# miniSystrm.net
KiCad netlist of a schematic drawn in Altium Designer
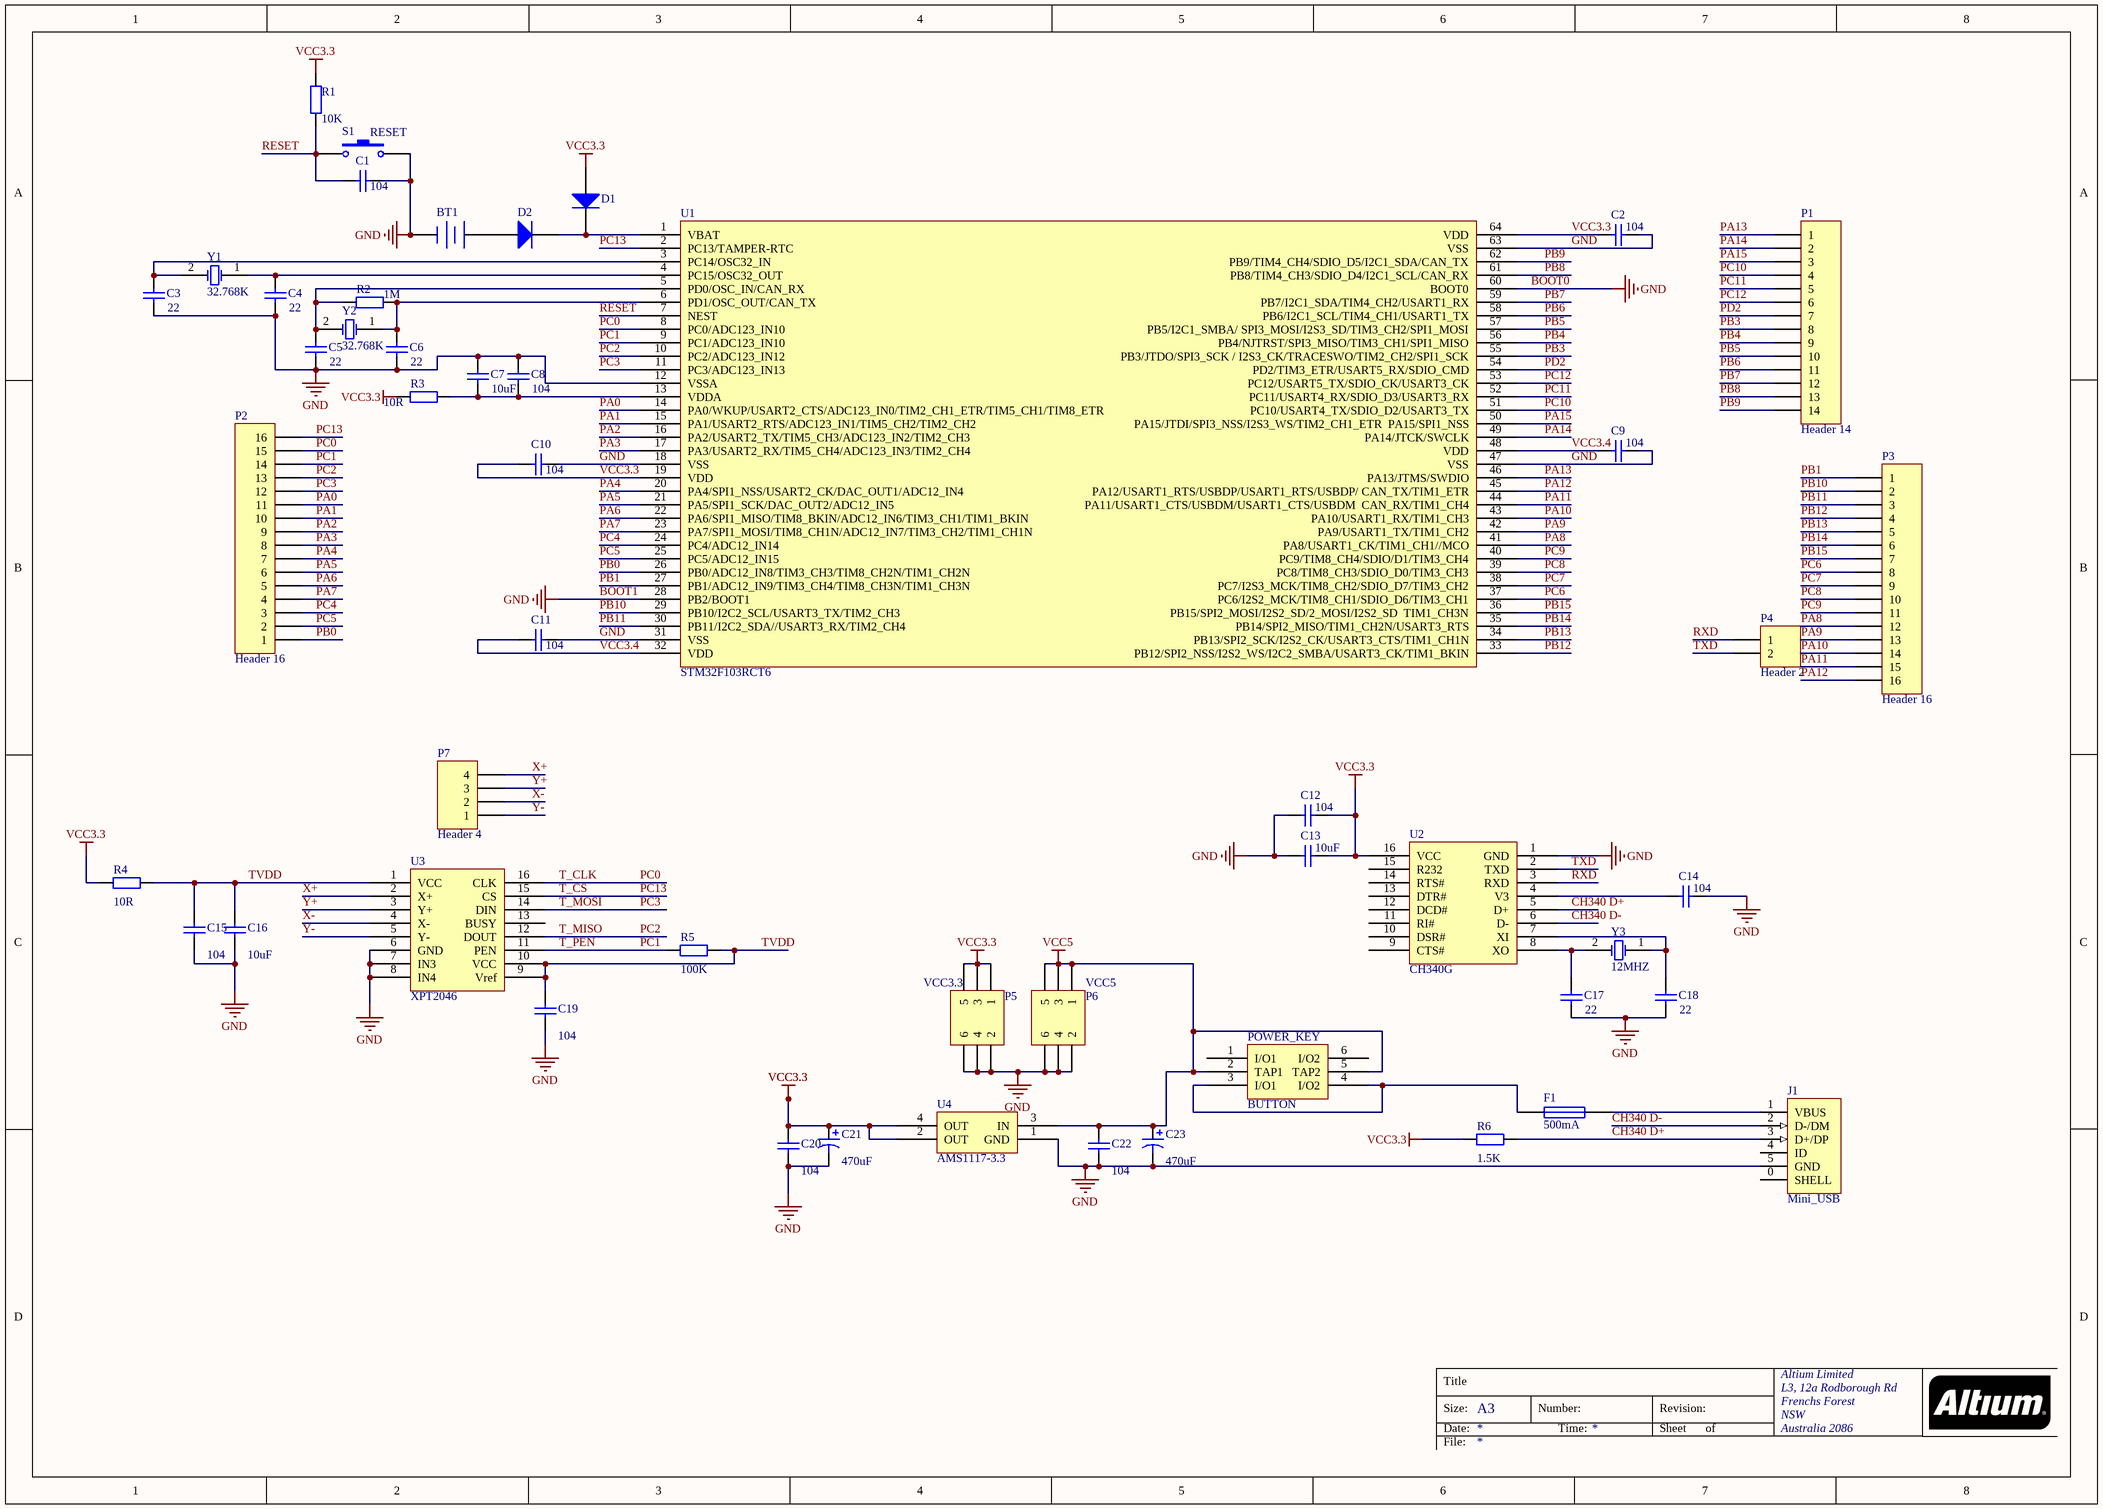
[diagram p0: miniSystrm.SchDoc]

(export (version "E")
  (design (tool "Eeschema 10.0.6"))
  (components
    (comp (ref "BT1")
      (value "~")
      (footprint "BAT-2")
      (description "Multicell Battery")
      (fields (field (name "PUBLISHER") "Altium Limited"))
      (libsource (lib "Miscellaneous Devices") (part "Battery"))
    )
    (comp (ref "C1")
      (value "104")
      (footprint "CAP-0603")
      (description "Capacitor")
      (fields (field (name "PUBLISHER") "Altium Limited"))
      (libsource (lib "Miscellaneous Devices") (part "Cap"))
    )
    (comp (ref "C2")
      (value "104")
      (footprint "CAP-0603")
      (description "Capacitor")
      (fields (field (name "PUBLISHER") "Altium Limited"))
      (libsource (lib "Miscellaneous Devices") (part "Cap"))
    )
    (comp (ref "C3")
      (value "22")
      (footprint "CAP-0603")
      (description "Capacitor")
      (fields (field (name "PUBLISHER") "Altium Limited"))
      (libsource (lib "Miscellaneous Devices") (part "Cap"))
    )
    (comp (ref "C4")
      (value "22")
      (footprint "CAP-0603")
      (description "Capacitor")
      (fields (field (name "PUBLISHER") "Altium Limited"))
      (libsource (lib "Miscellaneous Devices") (part "Cap"))
    )
    (comp (ref "C5")
      (value "22")
      (footprint "CAP-0603")
      (description "Capacitor")
      (fields (field (name "PUBLISHER") "Altium Limited"))
      (libsource (lib "Miscellaneous Devices") (part "Cap"))
    )
    (comp (ref "C6")
      (value "22")
      (footprint "CAP-0603")
      (description "Capacitor")
      (fields (field (name "PUBLISHER") "Altium Limited"))
      (libsource (lib "Miscellaneous Devices") (part "Cap"))
    )
    (comp (ref "C7")
      (value "10uF")
      (footprint "CAP-0603")
      (description "Capacitor")
      (fields (field (name "PUBLISHER") "Altium Limited"))
      (libsource (lib "Miscellaneous Devices") (part "Cap"))
    )
    (comp (ref "C8")
      (value "104")
      (footprint "CAP-0603")
      (description "Capacitor")
      (fields (field (name "PUBLISHER") "Altium Limited"))
      (libsource (lib "Miscellaneous Devices") (part "Cap"))
    )
    (comp (ref "C9")
      (value "104")
      (footprint "CAP-0603")
      (description "Capacitor")
      (fields (field (name "PUBLISHER") "Altium Limited"))
      (libsource (lib "Miscellaneous Devices") (part "Cap"))
    )
    (comp (ref "C10")
      (value "104")
      (footprint "CAP-0603")
      (description "Capacitor")
      (fields (field (name "PUBLISHER") "Altium Limited"))
      (libsource (lib "Miscellaneous Devices") (part "Cap"))
    )
    (comp (ref "C11")
      (value "104")
      (footprint "CAP-0603")
      (description "Capacitor")
      (fields (field (name "PUBLISHER") "Altium Limited"))
      (libsource (lib "Miscellaneous Devices") (part "Cap"))
    )
    (comp (ref "C12")
      (value "104")
      (footprint "CAP-0603")
      (description "Capacitor")
      (fields (field (name "PUBLISHER") "Altium Limited"))
      (libsource (lib "Miscellaneous Devices") (part "Cap"))
    )
    (comp (ref "C13")
      (value "10uF")
      (footprint "CAP-0603")
      (description "Capacitor")
      (fields (field (name "PUBLISHER") "Altium Limited"))
      (libsource (lib "Miscellaneous Devices") (part "Cap"))
    )
    (comp (ref "C14")
      (value "104")
      (footprint "CAP-0603")
      (description "Capacitor")
      (fields (field (name "PUBLISHER") "Altium Limited"))
      (libsource (lib "Miscellaneous Devices") (part "Cap"))
    )
    (comp (ref "C15")
      (value "104")
      (footprint "CAP-0603")
      (description "Capacitor")
      (fields (field (name "PUBLISHER") "Altium Limited"))
      (libsource (lib "Miscellaneous Devices") (part "Cap"))
    )
    (comp (ref "C16")
      (value "10uF")
      (footprint "CAP-0603")
      (description "Capacitor")
      (fields (field (name "PUBLISHER") "Altium Limited"))
      (libsource (lib "Miscellaneous Devices") (part "Cap"))
    )
    (comp (ref "C17")
      (value "22")
      (footprint "CAP-0603")
      (description "Capacitor")
      (fields (field (name "PUBLISHER") "Altium Limited"))
      (libsource (lib "Miscellaneous Devices") (part "Cap"))
    )
    (comp (ref "C18")
      (value "22")
      (footprint "CAP-0603")
      (description "Capacitor")
      (fields (field (name "PUBLISHER") "Altium Limited"))
      (libsource (lib "Miscellaneous Devices") (part "Cap"))
    )
    (comp (ref "C19")
      (value "104")
      (footprint "CAP-0603")
      (description "Capacitor")
      (fields (field (name "PUBLISHER") "Altium Limited"))
      (libsource (lib "Miscellaneous Devices") (part "Cap"))
    )
    (comp (ref "C20")
      (value "104")
      (footprint "CAP-0603")
      (description "Capacitor")
      (fields (field (name "PUBLISHER") "Altium Limited"))
      (libsource (lib "Miscellaneous Devices") (part "Cap"))
    )
    (comp (ref "C21")
      (value "470uF")
      (footprint "CAP-7343")
      (description "Polarized Capacitor (Radial)")
      (fields (field (name "PUBLISHER") "Altium Limited"))
      (libsource (lib "Miscellaneous Devices") (part "Cap Pol1"))
    )
    (comp (ref "C22")
      (value "104")
      (footprint "CAP-0603")
      (description "Capacitor")
      (fields (field (name "PUBLISHER") "Altium Limited"))
      (libsource (lib "Miscellaneous Devices") (part "Cap"))
    )
    (comp (ref "C23")
      (value "470uF")
      (footprint "CAP-7343")
      (description "Polarized Capacitor (Radial)")
      (fields (field (name "PUBLISHER") "Altium Limited"))
      (libsource (lib "Miscellaneous Devices") (part "Cap Pol1"))
    )
    (comp (ref "D1")
      (value "~")
      (footprint "DIODE-SMA")
      (description "1 Amp General Purpose Rectifier")
      (fields (field (name "PUBLISHER") "Altium Limited"))
      (libsource (lib "Miscellaneous Devices") (part "Diode 1N4001"))
    )
    (comp (ref "D2")
      (value "~")
      (footprint "DIODE-SMA")
      (description "1 Amp General Purpose Rectifier")
      (fields (field (name "PUBLISHER") "Altium Limited"))
      (libsource (lib "Miscellaneous Devices") (part "Diode 1N4001"))
    )
    (comp (ref "F1")
      (value "500mA")
      (footprint "PIN-W2/E2.8")
      (description "Fuse")
      (fields (field (name "PUBLISHER") "Altium Limited"))
      (libsource (lib "Miscellaneous Devices") (part "Fuse 1"))
    )
    (comp (ref "J1")
      (value "Mini_USB")
      (footprint "miniUSB")
      (description "USB 2.0, Right Angle, SMT, B Type, Receptacle, 5 Position, Black")
      (fields (field (name "PUBLISHER") "Altium Limited"))
      (libsource (lib "SkyWorks2") (part "Mini_USB"))
    )
    (comp (ref "P1")
      (value "Header 14")
      (footprint "HDR1X14")
      (description "Header, 14-Pin")
      (fields (field (name "PUBLISHER") "Altium Limited"))
      (libsource (lib "Miscellaneous Connectors") (part "Header 14"))
    )
    (comp (ref "P2")
      (value "Header 16")
      (footprint "HDR1X16")
      (description "Header, 16-Pin")
      (fields (field (name "PUBLISHER") "Altium Limited"))
      (libsource (lib "") (part "Header 16_1"))
    )
    (comp (ref "P3")
      (value "Header 16")
      (footprint "HDR1X16")
      (description "Header, 16-Pin")
      (fields (field (name "PUBLISHER") "Altium Limited"))
      (libsource (lib "Miscellaneous Connectors") (part "Header 16"))
    )
    (comp (ref "P4")
      (value "Header 2")
      (footprint "HDR1X2")
      (description "Header, 2-Pin")
      (fields (field (name "PUBLISHER") "Altium Limited"))
      (libsource (lib "Miscellaneous Connectors") (part "Header 2"))
    )
    (comp (ref "P5")
      (value "VCC3.3")
      (footprint "HDR2X3")
      (description "Header, 3-Pin, Dual row")
      (fields (field (name "PUBLISHER") "Altium Limited"))
      (libsource (lib "Miscellaneous Connectors") (part "Header 3X2"))
    )
    (comp (ref "P6")
      (value "VCC5")
      (footprint "HDR2X3")
      (description "Header, 3-Pin, Dual row")
      (fields (field (name "PUBLISHER") "Altium Limited"))
      (libsource (lib "Miscellaneous Connectors") (part "Header 3X2"))
    )
    (comp (ref "P7")
      (value "Header 4")
      (footprint "HDR1X4")
      (description "Header, 4-Pin")
      (fields (field (name "PUBLISHER") "Altium Limited"))
      (libsource (lib "Miscellaneous Connectors") (part "Header 4"))
    )
    (comp (ref "POWER_KEY") (value "BUTTON") (footprint "六脚自锁开关") (libsource (lib "BUTTON") (part "BUTTON")))
    (comp (ref "R1")
      (value "10K")
      (footprint "RES-0603")
      (description "Resistor")
      (fields (field (name "PUBLISHER") "Altium Limited"))
      (libsource (lib "") (part "Res2_2"))
    )
    (comp (ref "R2")
      (value "1M")
      (footprint "RES-0603")
      (description "Resistor")
      (fields (field (name "PUBLISHER") "Altium Limited"))
      (libsource (lib "") (part "Res2_1"))
    )
    (comp (ref "R3")
      (value "10R")
      (footprint "RES-0603")
      (description "Resistor")
      (fields (field (name "PUBLISHER") "Altium Limited"))
      (libsource (lib "Miscellaneous Devices") (part "Res2"))
    )
    (comp (ref "R4")
      (value "10R")
      (footprint "RES-0603")
      (description "Resistor")
      (fields (field (name "PUBLISHER") "Altium Limited"))
      (libsource (lib "Miscellaneous Devices") (part "Res2"))
    )
    (comp (ref "R5")
      (value "100K")
      (footprint "RES-0603")
      (description "Resistor")
      (fields (field (name "PUBLISHER") "Altium Limited"))
      (libsource (lib "Miscellaneous Devices") (part "Res2"))
    )
    (comp (ref "R6")
      (value "1.5K")
      (footprint "RES-0603")
      (description "Resistor")
      (fields (field (name "PUBLISHER") "Altium Limited"))
      (libsource (lib "Miscellaneous Devices") (part "Res2"))
    )
    (comp (ref "S1")
      (value "RESET")
      (footprint "SPST-2")
      (description "Switch")
      (fields (field (name "PUBLISHER") "Altium Limited"))
      (libsource (lib "Miscellaneous Devices") (part "SW-PB"))
    )
    (comp (ref "U1")
      (value "STM32F103RCT6")
      (footprint "LQFP-64")
      (libsource (lib "STM32F103RCT6") (part "STM32F103RCT6"))
    )
    (comp (ref "U2") (value "CH340G") (footprint "SOP16") (libsource (lib "CH340G") (part "CH340G")))
    (comp (ref "U3") (value "XPT2046") (footprint "TSSOP-16") (libsource (lib "XPT2046") (part "XPT2046")))
    (comp (ref "U4")
      (value "AMS1117-3.3")
      (footprint "SOT223")
      (libsource (lib "AMS1117-3.3") (part "AMS1117-3.3"))
    )
    (comp (ref "Y1")
      (value "32.768K")
      (footprint "R38")
      (description "Crystal Oscillator")
      (fields (field (name "PUBLISHER") "Altium Limited"))
      (libsource (lib "Miscellaneous Devices") (part "XTAL"))
    )
    (comp (ref "Y2")
      (value "32.768K")
      (footprint "R38")
      (description "Crystal Oscillator")
      (fields (field (name "PUBLISHER") "Altium Limited"))
      (libsource (lib "Miscellaneous Devices") (part "XTAL"))
    )
    (comp (ref "Y3")
      (value "12MHZ")
      (footprint "R38")
      (description "Crystal Oscillator")
      (fields (field (name "PUBLISHER") "Altium Limited"))
      (libsource (lib "Miscellaneous Devices") (part "XTAL"))
    )
  )
  (nets
    (net (code "1") (name "/CH340 D+") (class "Default")
      (node (ref "J1") (pin "3") (pinfunction "D+/DP_3") (pintype "input"))
      (node (ref "R6") (pin "1") (pinfunction "1_1") (pintype "passive"))
      (node (ref "U2") (pin "5") (pinfunction "D+_5") (pintype "power_in"))
    )
    (net (code "2") (name "/CH340 D-") (class "Default")
      (node (ref "J1") (pin "2") (pinfunction "D-/DM_2") (pintype "input"))
      (node (ref "U2") (pin "6") (pinfunction "D-_6") (pintype "power_in"))
    )
    (net (code "3") (name "/PA0") (class "Default")
      (node (ref "P2") (pin "11") (pinfunction "11_11") (pintype "passive"))
      (node (ref "U1") (pin "14") (pinfunction "PA0/WKUP/USART2_CTS/ADC123_IN0/TIM2_CH1_ETR/TIM5_CH1/TIM8_ETR_14") (pintype "power_in"))
    )
    (net (code "4") (name "/PA1") (class "Default")
      (node (ref "P2") (pin "10") (pinfunction "10_10") (pintype "passive"))
      (node (ref "U1") (pin "15") (pinfunction "PA1/USART2_RTS/ADC123_IN1/TIM5_CH2/TIM2_CH2_15") (pintype "power_in"))
    )
    (net (code "5") (name "/PA2") (class "Default")
      (node (ref "P2") (pin "9") (pinfunction "9_9") (pintype "passive"))
      (node (ref "U1") (pin "16") (pinfunction "PA2/USART2_TX/TIM5_CH3/ADC123_IN2/TIM2_CH3_16") (pintype "power_in"))
    )
    (net (code "6") (name "/PA3") (class "Default")
      (node (ref "P2") (pin "8") (pinfunction "8_8") (pintype "passive"))
      (node (ref "U1") (pin "17") (pinfunction "PA3/USART2_RX/TIM5_CH4/ADC123_IN3/TIM2_CH4_17") (pintype "power_in"))
    )
    (net (code "7") (name "/PA4") (class "Default")
      (node (ref "P2") (pin "7") (pinfunction "7_7") (pintype "passive"))
      (node (ref "U1") (pin "20") (pinfunction "PA4/SPI1_NSS/USART2_CK/DAC_OUT1/ADC12_IN4_20") (pintype "power_in"))
    )
    (net (code "8") (name "/PA5") (class "Default")
      (node (ref "P2") (pin "6") (pinfunction "6_6") (pintype "passive"))
      (node (ref "U1") (pin "21") (pinfunction "PA5/SPI1_SCK/DAC_OUT2/ADC12_IN5_21") (pintype "power_in"))
    )
    (net (code "9") (name "/PA6") (class "Default")
      (node (ref "P2") (pin "5") (pinfunction "5_5") (pintype "passive"))
      (node (ref "U1") (pin "22") (pinfunction "PA6/SPI1_MISO/TIM8_BKIN/ADC12_IN6/TIM3_CH1/TIM1_BKIN_22") (pintype "power_in"))
    )
    (net (code "10") (name "/PA7") (class "Default")
      (node (ref "P2") (pin "4") (pinfunction "4_4") (pintype "passive"))
      (node (ref "U1") (pin "23") (pinfunction "PA7/SPI1_MOSI/TIM8_CH1N/ADC12_IN7/TIM3_CH2/TIM1_CH1N_23") (pintype "power_in"))
    )
    (net (code "11") (name "/PA8") (class "Default")
      (node (ref "P3") (pin "12") (pinfunction "12_12") (pintype "passive"))
      (node (ref "U1") (pin "41") (pinfunction "PA8/USART1_CK/TIM1_CH1//MCO_41") (pintype "power_in"))
    )
    (net (code "12") (name "/PA9") (class "Default")
      (node (ref "P3") (pin "13") (pinfunction "13_13") (pintype "passive"))
      (node (ref "U1") (pin "42") (pinfunction "PA9/USART1_TX/TIM1_CH2_42") (pintype "power_in"))
    )
    (net (code "13") (name "/PA10") (class "Default")
      (node (ref "P3") (pin "14") (pinfunction "14_14") (pintype "passive"))
      (node (ref "U1") (pin "43") (pinfunction "PA10/USART1_RX/TIM1_CH3_43") (pintype "power_in"))
    )
    (net (code "14") (name "/PA11") (class "Default")
      (node (ref "P3") (pin "15") (pinfunction "15_15") (pintype "passive"))
      (node (ref "U1") (pin "44") (pinfunction "PA11/USART1_CTS/USBDM/USART1_CTS/USBDM__CAN_RX/TIM1_CH4_44") (pintype "power_in"))
    )
    (net (code "15") (name "/PA12") (class "Default")
      (node (ref "P3") (pin "16") (pinfunction "16_16") (pintype "passive"))
      (node (ref "U1") (pin "45") (pinfunction "PA12/USART1_RTS/USBDP/USART1_RTS/USBDP/_CAN_TX/TIM1_ETR_45") (pintype "power_in"))
    )
    (net (code "16") (name "/PA13") (class "Default")
      (node (ref "P1") (pin "1") (pinfunction "1_1") (pintype "passive"))
      (node (ref "U1") (pin "46") (pinfunction "PA13/JTMS/SWDIO_46") (pintype "power_in"))
    )
    (net (code "17") (name "/PA14") (class "Default")
      (node (ref "P1") (pin "2") (pinfunction "2_2") (pintype "passive"))
      (node (ref "U1") (pin "49") (pinfunction "PA14/JTCK/SWCLK_49") (pintype "power_in"))
    )
    (net (code "18") (name "/PA15") (class "Default")
      (node (ref "P1") (pin "3") (pinfunction "3_3") (pintype "passive"))
      (node (ref "U1") (pin "50") (pinfunction "PA15/JTDI/SPI3_NSS/I2S3_WS/TIM2_CH1_ETR__PA15/SPI1_NSS_50") (pintype "power_in"))
    )
    (net (code "19") (name "/PB0") (class "Default")
      (node (ref "P2") (pin "1") (pinfunction "1_1") (pintype "passive"))
      (node (ref "U1") (pin "26") (pinfunction "PB0/ADC12_IN8/TIM3_CH3/TIM8_CH2N/TIM1_CH2N_26") (pintype "power_in"))
    )
    (net (code "20") (name "/PB1") (class "Default")
      (node (ref "P3") (pin "1") (pinfunction "1_1") (pintype "passive"))
      (node (ref "U1") (pin "27") (pinfunction "PB1/ADC12_IN9/TIM3_CH4/TIM8_CH3N/TIM1_CH3N_27") (pintype "power_in"))
    )
    (net (code "21") (name "/PB3") (class "Default")
      (node (ref "P1") (pin "8") (pinfunction "8_8") (pintype "passive"))
      (node (ref "U1") (pin "55") (pinfunction "PB3/JTDO/SPI3_SCK_/_I2S3_CK/TRACESWO/TIM2_CH2/SPI1_SCK_55") (pintype "power_in"))
    )
    (net (code "22") (name "/PB4") (class "Default")
      (node (ref "P1") (pin "9") (pinfunction "9_9") (pintype "passive"))
      (node (ref "U1") (pin "56") (pinfunction "PB4/NJTRST/SPI3_MISO/TIM3_CH1/SPI1_MISO_56") (pintype "power_in"))
    )
    (net (code "23") (name "/PB5") (class "Default")
      (node (ref "P1") (pin "10") (pinfunction "10_10") (pintype "passive"))
      (node (ref "U1") (pin "57") (pinfunction "PB5/I2C1_SMBA/_SPI3_MOSI/I2S3_SD/TIM3_CH2/SPI1_MOSI_57") (pintype "power_in"))
    )
    (net (code "24") (name "/PB6") (class "Default")
      (node (ref "P1") (pin "11") (pinfunction "11_11") (pintype "passive"))
      (node (ref "U1") (pin "58") (pinfunction "PB6/I2C1_SCL/TIM4_CH1/USART1_TX_58") (pintype "power_in"))
    )
    (net (code "25") (name "/PB7") (class "Default")
      (node (ref "P1") (pin "12") (pinfunction "12_12") (pintype "passive"))
      (node (ref "U1") (pin "59") (pinfunction "PB7/I2C1_SDA/TIM4_CH2/USART1_RX_59") (pintype "power_in"))
    )
    (net (code "26") (name "/PB8") (class "Default")
      (node (ref "P1") (pin "13") (pinfunction "13_13") (pintype "passive"))
      (node (ref "U1") (pin "61") (pinfunction "PB8/TIM4_CH3/SDIO_D4/I2C1_SCL/CAN_RX_61") (pintype "power_in"))
    )
    (net (code "27") (name "/PB9") (class "Default")
      (node (ref "P1") (pin "14") (pinfunction "14_14") (pintype "passive"))
      (node (ref "U1") (pin "62") (pinfunction "PB9/TIM4_CH4/SDIO_D5/I2C1_SDA/CAN_TX_62") (pintype "power_in"))
    )
    (net (code "28") (name "/PB10") (class "Default")
      (node (ref "P3") (pin "2") (pinfunction "2_2") (pintype "passive"))
      (node (ref "U1") (pin "29") (pinfunction "PB10/I2C2_SCL/USART3_TX/TIM2_CH3_29") (pintype "power_in"))
    )
    (net (code "29") (name "/PB11") (class "Default")
      (node (ref "P3") (pin "3") (pinfunction "3_3") (pintype "passive"))
      (node (ref "U1") (pin "30") (pinfunction "PB11/I2C2_SDA//USART3_RX/TIM2_CH4_30") (pintype "power_in"))
    )
    (net (code "30") (name "/PB12") (class "Default")
      (node (ref "P3") (pin "4") (pinfunction "4_4") (pintype "passive"))
      (node (ref "U1") (pin "33") (pinfunction "PB12/SPI2_NSS/I2S2_WS/I2C2_SMBA/USART3_CK/TIM1_BKIN_33") (pintype "power_in"))
    )
    (net (code "31") (name "/PB13") (class "Default")
      (node (ref "P3") (pin "5") (pinfunction "5_5") (pintype "passive"))
      (node (ref "U1") (pin "34") (pinfunction "PB13/SPI2_SCK/I2S2_CK/USART3_CTS/TIM1_CH1N_34") (pintype "power_in"))
    )
    (net (code "32") (name "/PB14") (class "Default")
      (node (ref "P3") (pin "6") (pinfunction "6_6") (pintype "passive"))
      (node (ref "U1") (pin "35") (pinfunction "PB14/SPI2_MISO/TIM1_CH2N/USART3_RTS_35") (pintype "power_in"))
    )
    (net (code "33") (name "/PB15") (class "Default")
      (node (ref "P3") (pin "7") (pinfunction "7_7") (pintype "passive"))
      (node (ref "U1") (pin "36") (pinfunction "PB15/SPI2_MOSI/I2S2_SD/2_MOSI/I2S2_SD__TIM1_CH3N_36") (pintype "power_in"))
    )
    (net (code "34") (name "/PC0") (class "Default")
      (node (ref "P2") (pin "15") (pinfunction "15_15") (pintype "passive"))
      (node (ref "U1") (pin "8") (pinfunction "PC0/ADC123_IN10_8") (pintype "power_in"))
      (node (ref "U3") (pin "16") (pinfunction "CLK_16") (pintype "power_in"))
    )
    (net (code "35") (name "/PC1") (class "Default")
      (node (ref "P2") (pin "14") (pinfunction "14_14") (pintype "passive"))
      (node (ref "R5") (pin "2") (pinfunction "2_2") (pintype "passive"))
      (node (ref "U1") (pin "9") (pinfunction "PC1/ADC123_IN10_9") (pintype "power_in"))
      (node (ref "U3") (pin "11") (pinfunction "PEN_11") (pintype "power_in"))
    )
    (net (code "36") (name "/PC2") (class "Default")
      (node (ref "P2") (pin "13") (pinfunction "13_13") (pintype "passive"))
      (node (ref "U1") (pin "10") (pinfunction "PC2/ADC123_IN12_10") (pintype "power_in"))
      (node (ref "U3") (pin "12") (pinfunction "DOUT_12") (pintype "power_in"))
    )
    (net (code "37") (name "/PC3") (class "Default")
      (node (ref "P2") (pin "12") (pinfunction "12_12") (pintype "passive"))
      (node (ref "U1") (pin "11") (pinfunction "PC3/ADC123_IN13_11") (pintype "power_in"))
      (node (ref "U3") (pin "14") (pinfunction "DIN_14") (pintype "power_in"))
    )
    (net (code "38") (name "/PC4") (class "Default")
      (node (ref "P2") (pin "3") (pinfunction "3_3") (pintype "passive"))
      (node (ref "U1") (pin "24") (pinfunction "PC4/ADC12_IN14_24") (pintype "power_in"))
    )
    (net (code "39") (name "/PC5") (class "Default")
      (node (ref "P2") (pin "2") (pinfunction "2_2") (pintype "passive"))
      (node (ref "U1") (pin "25") (pinfunction "PC5/ADC12_IN15_25") (pintype "power_in"))
    )
    (net (code "40") (name "/PC6") (class "Default")
      (node (ref "P3") (pin "8") (pinfunction "8_8") (pintype "passive"))
      (node (ref "U1") (pin "37") (pinfunction "PC6/I2S2_MCK/TIM8_CH1/SDIO_D6/TIM3_CH1_37") (pintype "power_in"))
    )
    (net (code "41") (name "/PC7") (class "Default")
      (node (ref "P3") (pin "9") (pinfunction "9_9") (pintype "passive"))
      (node (ref "U1") (pin "38") (pinfunction "PC7/I2S3_MCK/TIM8_CH2/SDIO_D7/TIM3_CH2_38") (pintype "power_in"))
    )
    (net (code "42") (name "/PC8") (class "Default")
      (node (ref "P3") (pin "10") (pinfunction "10_10") (pintype "passive"))
      (node (ref "U1") (pin "39") (pinfunction "PC8/TIM8_CH3/SDIO_D0/TIM3_CH3_39") (pintype "power_in"))
    )
    (net (code "43") (name "/PC9") (class "Default")
      (node (ref "P3") (pin "11") (pinfunction "11_11") (pintype "passive"))
      (node (ref "U1") (pin "40") (pinfunction "PC9/TIM8_CH4/SDIO/D1/TIM3_CH4_40") (pintype "power_in"))
    )
    (net (code "44") (name "/PC10") (class "Default")
      (node (ref "P1") (pin "4") (pinfunction "4_4") (pintype "passive"))
      (node (ref "U1") (pin "51") (pinfunction "PC10/USART4_TX/SDIO_D2/USART3_TX_51") (pintype "power_in"))
    )
    (net (code "45") (name "/PC11") (class "Default")
      (node (ref "P1") (pin "5") (pinfunction "5_5") (pintype "passive"))
      (node (ref "U1") (pin "52") (pinfunction "PC11/USART4_RX/SDIO_D3/USART3_RX_52") (pintype "power_in"))
    )
    (net (code "46") (name "/PC12") (class "Default")
      (node (ref "P1") (pin "6") (pinfunction "6_6") (pintype "passive"))
      (node (ref "U1") (pin "53") (pinfunction "PC12/USART5_TX/SDIO_CK/USART3_CK_53") (pintype "power_in"))
    )
    (net (code "47") (name "/PC13") (class "Default")
      (node (ref "P2") (pin "16") (pinfunction "16_16") (pintype "passive"))
      (node (ref "U1") (pin "2") (pinfunction "PC13/TAMPER-RTC_2") (pintype "power_in"))
      (node (ref "U3") (pin "15") (pinfunction "CS_15") (pintype "power_in"))
    )
    (net (code "48") (name "/PD2") (class "Default")
      (node (ref "P1") (pin "7") (pinfunction "7_7") (pintype "passive"))
      (node (ref "U1") (pin "54") (pinfunction "PD2/TIM3_ETR/USART5_RX/SDIO_CMD_54") (pintype "power_in"))
    )
    (net (code "49") (name "/RESET") (class "Default")
      (node (ref "C1") (pin "2") (pinfunction "2_2") (pintype "passive"))
      (node (ref "R1") (pin "1") (pinfunction "1_1") (pintype "passive"))
      (node (ref "S1") (pin "1") (pinfunction "1_1") (pintype "passive"))
      (node (ref "U1") (pin "7") (pinfunction "NEST_7") (pintype "power_in"))
    )
    (net (code "50") (name "/RXD") (class "Default")
      (node (ref "P4") (pin "1") (pinfunction "1_1") (pintype "passive"))
      (node (ref "U2") (pin "3") (pinfunction "RXD_3") (pintype "power_in"))
    )
    (net (code "51") (name "/TVDD") (class "Default")
      (node (ref "C15") (pin "1") (pinfunction "1_1") (pintype "passive"))
      (node (ref "C16") (pin "1") (pinfunction "1_1") (pintype "passive"))
      (node (ref "C19") (pin "1") (pinfunction "1_1") (pintype "passive"))
      (node (ref "R4") (pin "1") (pinfunction "1_1") (pintype "passive"))
      (node (ref "R5") (pin "1") (pinfunction "1_1") (pintype "passive"))
      (node (ref "U3") (pin "1") (pinfunction "VCC_1") (pintype "power_in"))
      (node (ref "U3") (pin "10") (pinfunction "VCC_10") (pintype "power_in"))
      (node (ref "U3") (pin "9") (pinfunction "Vref_9") (pintype "power_in"))
    )
    (net (code "52") (name "/TXD") (class "Default")
      (node (ref "P4") (pin "2") (pinfunction "2_2") (pintype "passive"))
      (node (ref "U2") (pin "2") (pinfunction "TXD_2") (pintype "power_in"))
    )
    (net (code "53") (name "/VCC3.4") (class "Default")
      (node (ref "C11") (pin "2") (pinfunction "2_2") (pintype "passive"))
      (node (ref "C9") (pin "2") (pinfunction "2_2") (pintype "passive"))
      (node (ref "U1") (pin "32") (pinfunction "VDD_32") (pintype "power_in"))
      (node (ref "U1") (pin "48") (pinfunction "VDD_48") (pintype "power_in"))
    )
    (net (code "54") (name "/X+") (class "Default")
      (node (ref "P7") (pin "4") (pinfunction "4_4") (pintype "passive"))
      (node (ref "U3") (pin "2") (pinfunction "X+_2") (pintype "power_in"))
    )
    (net (code "55") (name "/X-") (class "Default")
      (node (ref "P7") (pin "2") (pinfunction "2_2") (pintype "passive"))
      (node (ref "U3") (pin "4") (pinfunction "X-_4") (pintype "power_in"))
    )
    (net (code "56") (name "/Y+") (class "Default")
      (node (ref "P7") (pin "3") (pinfunction "3_3") (pintype "passive"))
      (node (ref "U3") (pin "3") (pinfunction "Y+_3") (pintype "power_in"))
    )
    (net (code "57") (name "/Y-") (class "Default")
      (node (ref "P7") (pin "1") (pinfunction "1_1") (pintype "passive"))
      (node (ref "U3") (pin "5") (pinfunction "Y-_5") (pintype "power_in"))
    )
    (net (code "58") (name "GND") (class "Default")
      (node (ref "BT1") (pin "2") (pinfunction "-_2") (pintype "passive"))
      (node (ref "C1") (pin "1") (pinfunction "1_1") (pintype "passive"))
      (node (ref "C10") (pin "1") (pinfunction "1_1") (pintype "passive"))
      (node (ref "C11") (pin "1") (pinfunction "1_1") (pintype "passive"))
      (node (ref "C12") (pin "2") (pinfunction "2_2") (pintype "passive"))
      (node (ref "C13") (pin "2") (pinfunction "2_2") (pintype "passive"))
      (node (ref "C14") (pin "1") (pinfunction "1_1") (pintype "passive"))
      (node (ref "C15") (pin "2") (pinfunction "2_2") (pintype "passive"))
      (node (ref "C16") (pin "2") (pinfunction "2_2") (pintype "passive"))
      (node (ref "C17") (pin "1") (pinfunction "1_1") (pintype "passive"))
      (node (ref "C18") (pin "1") (pinfunction "1_1") (pintype "passive"))
      (node (ref "C19") (pin "2") (pinfunction "2_2") (pintype "passive"))
      (node (ref "C2") (pin "1") (pinfunction "1_1") (pintype "passive"))
      (node (ref "C20") (pin "2") (pinfunction "2_2") (pintype "passive"))
      (node (ref "C21") (pin "2") (pinfunction "2_2") (pintype "passive"))
      (node (ref "C22") (pin "2") (pinfunction "2_2") (pintype "passive"))
      (node (ref "C23") (pin "2") (pinfunction "2_2") (pintype "passive"))
      (node (ref "C3") (pin "1") (pinfunction "1_1") (pintype "passive"))
      (node (ref "C4") (pin "1") (pinfunction "1_1") (pintype "passive"))
      (node (ref "C5") (pin "1") (pinfunction "1_1") (pintype "passive"))
      (node (ref "C6") (pin "1") (pinfunction "1_1") (pintype "passive"))
      (node (ref "C7") (pin "1") (pinfunction "1_1") (pintype "passive"))
      (node (ref "C8") (pin "2") (pinfunction "2_2") (pintype "passive"))
      (node (ref "C9") (pin "1") (pinfunction "1_1") (pintype "passive"))
      (node (ref "J1") (pin "5") (pinfunction "GND_5") (pintype "passive"))
      (node (ref "P5") (pin "2") (pinfunction "2_2") (pintype "passive"))
      (node (ref "P5") (pin "4") (pinfunction "4_4") (pintype "passive"))
      (node (ref "P5") (pin "6") (pinfunction "6_6") (pintype "passive"))
      (node (ref "P6") (pin "2") (pinfunction "2_2") (pintype "passive"))
      (node (ref "P6") (pin "4") (pinfunction "4_4") (pintype "passive"))
      (node (ref "P6") (pin "6") (pinfunction "6_6") (pintype "passive"))
      (node (ref "S1") (pin "2") (pinfunction "2_2") (pintype "passive"))
      (node (ref "U1") (pin "12") (pinfunction "VSSA_12") (pintype "power_in"))
      (node (ref "U1") (pin "18") (pinfunction "VSS_18") (pintype "power_in"))
      (node (ref "U1") (pin "28") (pinfunction "PB2/BOOT1_28") (pintype "power_in"))
      (node (ref "U1") (pin "31") (pinfunction "VSS_31") (pintype "power_in"))
      (node (ref "U1") (pin "47") (pinfunction "VSS_47") (pintype "power_in"))
      (node (ref "U1") (pin "60") (pinfunction "BOOT0_60") (pintype "power_in"))
      (node (ref "U1") (pin "63") (pinfunction "VSS_63") (pintype "power_in"))
      (node (ref "U2") (pin "1") (pinfunction "GND_1") (pintype "power_in"))
      (node (ref "U3") (pin "6") (pinfunction "GND_6") (pintype "power_in"))
      (node (ref "U3") (pin "7") (pinfunction "IN3_7") (pintype "power_in"))
      (node (ref "U3") (pin "8") (pinfunction "IN4_8") (pintype "power_in"))
      (node (ref "U4") (pin "1") (pinfunction "GND_1") (pintype "power_in"))
    )
    (net (code "59") (name "Net-(BT1-+)") (class "Default")
      (node (ref "BT1") (pin "1") (pinfunction "+_1") (pintype "passive"))
      (node (ref "D2") (pin "1") (pinfunction "A_1") (pintype "passive"))
    )
    (net (code "60") (name "Net-(D1-K)") (class "Default")
      (node (ref "D1") (pin "2") (pinfunction "K_2") (pintype "passive"))
      (node (ref "D2") (pin "2") (pinfunction "K_2") (pintype "passive"))
      (node (ref "U1") (pin "1") (pinfunction "VBAT_1") (pintype "power_in"))
    )
    (net (code "61") (name "Net-(F1-Pad1)") (class "Default")
      (node (ref "F1") (pin "1") (pinfunction "1_1") (pintype "passive"))
      (node (ref "POWER_KEY") (pin "3") (pinfunction "I/O1_3") (pintype "power_in"))
      (node (ref "POWER_KEY") (pin "4") (pinfunction "I/O2_4") (pintype "power_in"))
    )
    (net (code "62") (name "Net-(J1-VBUS)") (class "Default")
      (node (ref "F1") (pin "2") (pinfunction "2_2") (pintype "passive"))
      (node (ref "J1") (pin "1") (pinfunction "VBUS_1") (pintype "power_in"))
    )
    (net (code "63") (name "Net-(U1-PC14{slash}OSC32_IN)") (class "Default")
      (node (ref "C3") (pin "2") (pinfunction "2_2") (pintype "passive"))
      (node (ref "U1") (pin "3") (pinfunction "PC14/OSC32_IN_3") (pintype "power_in"))
      (node (ref "Y1") (pin "2") (pinfunction "OSC2_2") (pintype "passive"))
    )
    (net (code "64") (name "Net-(U1-PC15{slash}OSC32_OUT)") (class "Default")
      (node (ref "C4") (pin "2") (pinfunction "2_2") (pintype "passive"))
      (node (ref "U1") (pin "4") (pinfunction "PC15/OSC32_OUT_4") (pintype "power_in"))
      (node (ref "Y1") (pin "1") (pinfunction "OSC1_1") (pintype "passive"))
    )
    (net (code "65") (name "Net-(U1-PD0{slash}OSC_IN{slash}CAN_RX)") (class "Default")
      (node (ref "C5") (pin "2") (pinfunction "2_2") (pintype "passive"))
      (node (ref "R2") (pin "1") (pinfunction "1_1") (pintype "passive"))
      (node (ref "U1") (pin "5") (pinfunction "PD0/OSC_IN/CAN_RX_5") (pintype "power_in"))
      (node (ref "Y2") (pin "2") (pinfunction "OSC2_2") (pintype "passive"))
    )
    (net (code "66") (name "Net-(U1-PD1{slash}OSC_OUT{slash}CAN_TX)") (class "Default")
      (node (ref "C6") (pin "2") (pinfunction "2_2") (pintype "passive"))
      (node (ref "R2") (pin "2") (pinfunction "2_2") (pintype "passive"))
      (node (ref "U1") (pin "6") (pinfunction "PD1/OSC_OUT/CAN_TX_6") (pintype "power_in"))
      (node (ref "Y2") (pin "1") (pinfunction "OSC1_1") (pintype "passive"))
    )
    (net (code "67") (name "Net-(U1-VDDA)") (class "Default")
      (node (ref "C7") (pin "2") (pinfunction "2_2") (pintype "passive"))
      (node (ref "C8") (pin "1") (pinfunction "1_1") (pintype "passive"))
      (node (ref "R3") (pin "1") (pinfunction "1_1") (pintype "passive"))
      (node (ref "U1") (pin "13") (pinfunction "VDDA_13") (pintype "power_in"))
    )
    (net (code "68") (name "Net-(U2-V3)") (class "Default")
      (node (ref "C14") (pin "2") (pinfunction "2_2") (pintype "passive"))
      (node (ref "U2") (pin "4") (pinfunction "V3_4") (pintype "power_in"))
    )
    (net (code "69") (name "Net-(U2-XI)") (class "Default")
      (node (ref "C18") (pin "2") (pinfunction "2_2") (pintype "passive"))
      (node (ref "U2") (pin "7") (pinfunction "XI_7") (pintype "power_in"))
      (node (ref "Y3") (pin "1") (pinfunction "OSC1_1") (pintype "passive"))
    )
    (net (code "70") (name "Net-(U2-XO)") (class "Default")
      (node (ref "C17") (pin "2") (pinfunction "2_2") (pintype "passive"))
      (node (ref "U2") (pin "8") (pinfunction "XO_8") (pintype "power_in"))
      (node (ref "Y3") (pin "2") (pinfunction "OSC2_2") (pintype "passive"))
    )
    (net (code "71") (name "VCC3.3") (class "Default")
      (node (ref "C10") (pin "2") (pinfunction "2_2") (pintype "passive"))
      (node (ref "C12") (pin "1") (pinfunction "1_1") (pintype "passive"))
      (node (ref "C13") (pin "1") (pinfunction "1_1") (pintype "passive"))
      (node (ref "C2") (pin "2") (pinfunction "2_2") (pintype "passive"))
      (node (ref "C20") (pin "1") (pinfunction "1_1") (pintype "passive"))
      (node (ref "C21") (pin "1") (pinfunction "1_1") (pintype "passive"))
      (node (ref "D1") (pin "1") (pinfunction "A_1") (pintype "passive"))
      (node (ref "P5") (pin "1") (pinfunction "1_1") (pintype "passive"))
      (node (ref "P5") (pin "3") (pinfunction "3_3") (pintype "passive"))
      (node (ref "P5") (pin "5") (pinfunction "5_5") (pintype "passive"))
      (node (ref "R1") (pin "2") (pinfunction "2_2") (pintype "passive"))
      (node (ref "R3") (pin "2") (pinfunction "2_2") (pintype "passive"))
      (node (ref "R4") (pin "2") (pinfunction "2_2") (pintype "passive"))
      (node (ref "R6") (pin "2") (pinfunction "2_2") (pintype "passive"))
      (node (ref "U1") (pin "19") (pinfunction "VDD_19") (pintype "power_in"))
      (node (ref "U1") (pin "64") (pinfunction "VDD_64") (pintype "power_in"))
      (node (ref "U2") (pin "16") (pinfunction "VCC_16") (pintype "power_in"))
      (node (ref "U4") (pin "2") (pinfunction "OUT_2") (pintype "power_in"))
      (node (ref "U4") (pin "4") (pinfunction "OUT_4") (pintype "power_in"))
    )
    (net (code "72") (name "VCC5") (class "Default")
      (node (ref "C22") (pin "1") (pinfunction "1_1") (pintype "passive"))
      (node (ref "C23") (pin "1") (pinfunction "1_1") (pintype "passive"))
      (node (ref "P6") (pin "1") (pinfunction "1_1") (pintype "passive"))
      (node (ref "P6") (pin "3") (pinfunction "3_3") (pintype "passive"))
      (node (ref "P6") (pin "5") (pinfunction "5_5") (pintype "passive"))
      (node (ref "POWER_KEY") (pin "2") (pinfunction "TAP1_2") (pintype "power_in"))
      (node (ref "POWER_KEY") (pin "5") (pinfunction "TAP2_5") (pintype "power_in"))
      (node (ref "U4") (pin "3") (pinfunction "IN_3") (pintype "power_in"))
    )
    (net (code "73") (name "unconnected-(J1-ID-Pad4)") (class "Default")
      (node (ref "J1") (pin "4") (pinfunction "ID_4") (pintype "power_in"))
    )
    (net (code "74") (name "unconnected-(J1-SHELL-Pad0)") (class "Default")
      (node (ref "J1") (pin "0") (pinfunction "SHELL_0") (pintype "passive"))
    )
    (net (code "75") (name "unconnected-(POWER_KEY-I{slash}O1-Pad1)") (class "Default")
      (node (ref "POWER_KEY") (pin "1") (pinfunction "I/O1_1") (pintype "power_in"))
    )
    (net (code "76") (name "unconnected-(POWER_KEY-I{slash}O2-Pad6)") (class "Default")
      (node (ref "POWER_KEY") (pin "6") (pinfunction "I/O2_6") (pintype "power_in"))
    )
    (net (code "77") (name "unconnected-(U2-CTS#-Pad9)") (class "Default")
      (node (ref "U2") (pin "9") (pinfunction "CTS#_9") (pintype "power_in"))
    )
    (net (code "78") (name "unconnected-(U2-DCD#-Pad12)") (class "Default")
      (node (ref "U2") (pin "12") (pinfunction "DCD#_12") (pintype "power_in"))
    )
    (net (code "79") (name "unconnected-(U2-DSR#-Pad10)") (class "Default")
      (node (ref "U2") (pin "10") (pinfunction "DSR#_10") (pintype "power_in"))
    )
    (net (code "80") (name "unconnected-(U2-DTR#-Pad13)") (class "Default")
      (node (ref "U2") (pin "13") (pinfunction "DTR#_13") (pintype "power_in"))
    )
    (net (code "81") (name "unconnected-(U2-R232-Pad15)") (class "Default")
      (node (ref "U2") (pin "15") (pinfunction "R232_15") (pintype "power_in"))
    )
    (net (code "82") (name "unconnected-(U2-RI#-Pad11)") (class "Default")
      (node (ref "U2") (pin "11") (pinfunction "RI#_11") (pintype "power_in"))
    )
    (net (code "83") (name "unconnected-(U2-RTS#-Pad14)") (class "Default")
      (node (ref "U2") (pin "14") (pinfunction "RTS#_14") (pintype "power_in"))
    )
    (net (code "84") (name "unconnected-(U3-BUSY-Pad13)") (class "Default")
      (node (ref "U3") (pin "13") (pinfunction "BUSY_13") (pintype "power_in"))
    )
  )
)
